# PROG328P.net
KiCad netlist of a schematic drawn in EAGLE
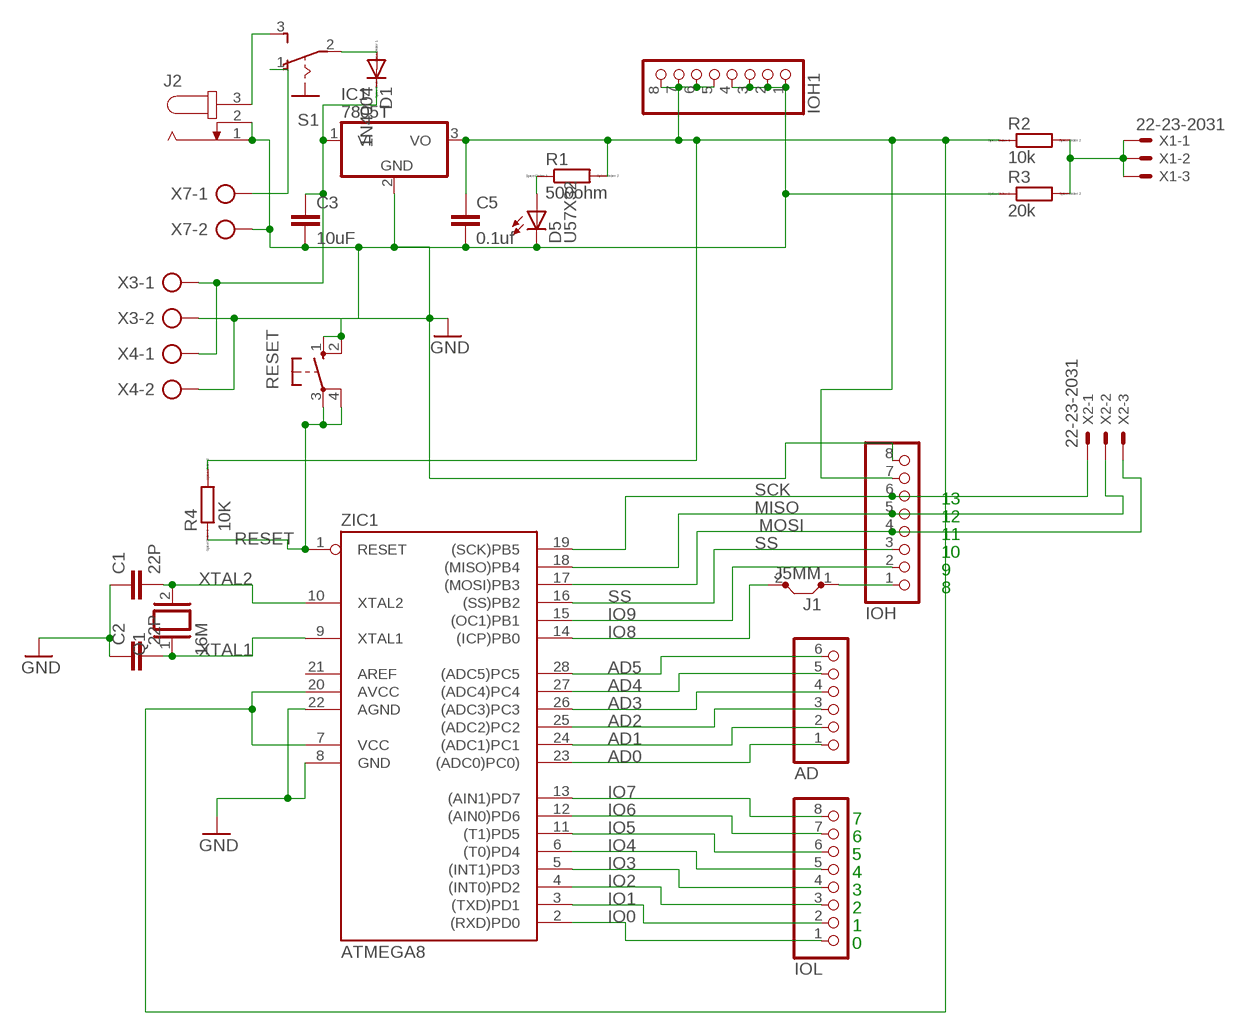
[diagram p0: schematic, sheet 1]

(export (version "E")
  (design (tool "Eeschema 10.0.6"))
  (components
    (comp (ref "AD")
      (value "PINHD-1X6")
      (footprint "eagle-import:1X06")
      (libsource (lib "eagle-import") (part "PINHD-1X6"))
    )
    (comp (ref "C1")
      (value "22P")
      (footprint "eagle-import:C2.5-6")
      (libsource (lib "eagle-import") (part "C2.5/6"))
    )
    (comp (ref "C2")
      (value "22P")
      (footprint "eagle-import:C2.5-6")
      (libsource (lib "eagle-import") (part "C2.5/6"))
    )
    (comp (ref "C3")
      (value "10uF")
      (footprint "eagle-import:C2.5-4")
      (libsource (lib "eagle-import") (part "C2.5/4"))
    )
    (comp (ref "C5")
      (value "0.1uf")
      (footprint "eagle-import:C2.5-4")
      (libsource (lib "eagle-import") (part "C2.5/4"))
    )
    (comp (ref "D1")
      (value "1N4004")
      (footprint "eagle-import:DO41-10")
      (libsource (lib "eagle-import") (part "1N4004"))
    )
    (comp (ref "D5")
      (value "U57X32")
      (footprint "eagle-import:U57X32")
      (libsource (lib "eagle-import") (part "U57X32"))
    )
    (comp (ref "IC1")
      (value "7805T")
      (footprint "eagle-import:TO220H")
      (libsource (lib "eagle-import") (part "78T05"))
    )
    (comp (ref "IOH")
      (value "PINHD-1X8")
      (footprint "eagle-import:1X08")
      (libsource (lib "eagle-import") (part "PINHD-1X8"))
    )
    (comp (ref "IOH1")
      (value "PINHD-1X8")
      (footprint "eagle-import:1X08")
      (libsource (lib "eagle-import") (part "PINHD-1X8"))
    )
    (comp (ref "IOL")
      (value "PINHD-1X8")
      (footprint "eagle-import:1X08")
      (libsource (lib "eagle-import") (part "PINHD-1X8"))
    )
    (comp (ref "J1")
      (value "J5MM")
      (footprint "eagle-import:05")
      (libsource (lib "eagle-import") (part "J5MM"))
    )
    (comp (ref "J2")
      (value "JACK-PLUG0")
      (footprint "eagle-import:SPC4077")
      (libsource (lib "eagle-import") (part "JACK-PLUG0"))
    )
    (comp (ref "Q1")
      (value "16M")
      (footprint "eagle-import:QS")
      (libsource (lib "eagle-import") (part "XTAL/S"))
    )
    (comp (ref "R1")
      (value "500ohm")
      (footprint "eagle-import:0207_10")
      (libsource (lib "eagle-import") (part "R0207/10"))
    )
    (comp (ref "R2")
      (value "10k")
      (footprint "eagle-import:0207_10")
      (libsource (lib "eagle-import") (part "R0207/10"))
    )
    (comp (ref "R3")
      (value "20k")
      (footprint "eagle-import:0207_10")
      (libsource (lib "eagle-import") (part "R0207/10"))
    )
    (comp (ref "R4")
      (value "10K")
      (footprint "eagle-import:0207_10")
      (libsource (lib "eagle-import") (part "R0207/10"))
    )
    (comp (ref "RESET")
      (value "10-XX")
      (footprint "eagle-import:B3F-10XX")
      (fields (field (name "MPN") "B3F-1000"))
      (libsource (lib "eagle-import") (part "10-XX"))
    )
    (comp (ref "S1")
      (value "255SB")
      (footprint "eagle-import:255SB")
      (libsource (lib "eagle-import") (part "255SB"))
    )
    (comp (ref "X1")
      (value "22-23-2031")
      (footprint "eagle-import:22-23-2031")
      (fields (field (name "MF") "MOLEX"))
      (libsource (lib "eagle-import") (part "22-23-2031"))
    )
    (comp (ref "X2")
      (value "22-23-2031")
      (footprint "eagle-import:22-23-2031")
      (fields (field (name "MF") "MOLEX"))
      (libsource (lib "eagle-import") (part "22-23-2031"))
    )
    (comp (ref "X3")
      (value "AK500/2-H")
      (footprint "eagle-import:AK500_2-H")
      (libsource (lib "eagle-import") (part "AK500/2-H"))
    )
    (comp (ref "X4")
      (value "AK500/2-H")
      (footprint "eagle-import:AK500_2-H")
      (libsource (lib "eagle-import") (part "AK500/2-H"))
    )
    (comp (ref "X7")
      (value "AK500/2-H")
      (footprint "eagle-import:AK500_2-H")
      (libsource (lib "eagle-import") (part "AK500/2-H"))
    )
    (comp (ref "ZIC1")
      (value "ATMEGA8")
      (footprint "eagle-import:DIL28-3")
      (libsource (lib "eagle-import") (part "AT90S4433P"))
    )
  )
  (nets
    (net (code "1") (name "/AD0") (class "Default")
      (node (ref "AD") (pin "1") (pinfunction "1_1") (pintype "passive"))
      (node (ref "ZIC1") (pin "23") (pinfunction "(ADC0)PC0)_23") (pintype "bidirectional"))
    )
    (net (code "2") (name "/AD1") (class "Default")
      (node (ref "AD") (pin "2") (pinfunction "2_2") (pintype "passive"))
      (node (ref "ZIC1") (pin "24") (pinfunction "(ADC1)PC1_24") (pintype "bidirectional"))
    )
    (net (code "3") (name "/AD2") (class "Default")
      (node (ref "AD") (pin "3") (pinfunction "3_3") (pintype "passive"))
      (node (ref "ZIC1") (pin "25") (pinfunction "(ADC2)PC2_25") (pintype "bidirectional"))
    )
    (net (code "4") (name "/AD3") (class "Default")
      (node (ref "AD") (pin "4") (pinfunction "4_4") (pintype "passive"))
      (node (ref "ZIC1") (pin "26") (pinfunction "(ADC3)PC3_26") (pintype "bidirectional"))
    )
    (net (code "5") (name "/AD4") (class "Default")
      (node (ref "AD") (pin "5") (pinfunction "5_5") (pintype "passive"))
      (node (ref "ZIC1") (pin "27") (pinfunction "(ADC4)PC4_27") (pintype "bidirectional"))
    )
    (net (code "6") (name "/AD5") (class "Default")
      (node (ref "AD") (pin "6") (pinfunction "6_6") (pintype "passive"))
      (node (ref "ZIC1") (pin "28") (pinfunction "(ADC5)PC5_28") (pintype "bidirectional"))
    )
    (net (code "7") (name "/IO0") (class "Default")
      (node (ref "IOL") (pin "1") (pinfunction "1_1") (pintype "passive"))
      (node (ref "ZIC1") (pin "2") (pinfunction "(RXD)PD0_2") (pintype "bidirectional"))
    )
    (net (code "8") (name "/IO1") (class "Default")
      (node (ref "IOL") (pin "2") (pinfunction "2_2") (pintype "passive"))
      (node (ref "ZIC1") (pin "3") (pinfunction "(TXD)PD1_3") (pintype "bidirectional"))
    )
    (net (code "9") (name "/IO2") (class "Default")
      (node (ref "IOL") (pin "3") (pinfunction "3_3") (pintype "passive"))
      (node (ref "ZIC1") (pin "4") (pinfunction "(INT0)PD2_4") (pintype "bidirectional"))
    )
    (net (code "10") (name "/IO3") (class "Default")
      (node (ref "IOL") (pin "4") (pinfunction "4_4") (pintype "passive"))
      (node (ref "ZIC1") (pin "5") (pinfunction "(INT1)PD3_5") (pintype "bidirectional"))
    )
    (net (code "11") (name "/IO4") (class "Default")
      (node (ref "IOL") (pin "5") (pinfunction "5_5") (pintype "passive"))
      (node (ref "ZIC1") (pin "6") (pinfunction "(T0)PD4_6") (pintype "bidirectional"))
    )
    (net (code "12") (name "/IO5") (class "Default")
      (node (ref "IOL") (pin "6") (pinfunction "6_6") (pintype "passive"))
      (node (ref "ZIC1") (pin "11") (pinfunction "(T1)PD5_11") (pintype "bidirectional"))
    )
    (net (code "13") (name "/IO6") (class "Default")
      (node (ref "IOL") (pin "7") (pinfunction "7_7") (pintype "passive"))
      (node (ref "ZIC1") (pin "12") (pinfunction "(AIN0)PD6_12") (pintype "bidirectional"))
    )
    (net (code "14") (name "/IO7") (class "Default")
      (node (ref "IOL") (pin "8") (pinfunction "8_8") (pintype "passive"))
      (node (ref "ZIC1") (pin "13") (pinfunction "(AIN1)PD7_13") (pintype "bidirectional"))
    )
    (net (code "15") (name "/IO8") (class "Default")
      (node (ref "J1") (pin "2") (pinfunction "2_2") (pintype "passive"))
      (node (ref "ZIC1") (pin "14") (pinfunction "(ICP)PB0_14") (pintype "bidirectional"))
    )
    (net (code "16") (name "/IO9") (class "Default")
      (node (ref "IOH") (pin "2") (pinfunction "2_2") (pintype "passive"))
      (node (ref "ZIC1") (pin "15") (pinfunction "(OC1)PB1_15") (pintype "bidirectional"))
    )
    (net (code "17") (name "/MISO") (class "Default")
      (node (ref "IOH") (pin "5") (pinfunction "5_5") (pintype "passive"))
      (node (ref "X2") (pin "2") (pinfunction "S_2") (pintype "passive"))
      (node (ref "ZIC1") (pin "18") (pinfunction "(MISO)PB4_18") (pintype "bidirectional"))
    )
    (net (code "18") (name "/MOSI") (class "Default")
      (node (ref "IOH") (pin "4") (pinfunction "4_4") (pintype "passive"))
      (node (ref "X2") (pin "3") (pinfunction "S_3") (pintype "passive"))
      (node (ref "ZIC1") (pin "17") (pinfunction "(MOSI)PB3_17") (pintype "bidirectional"))
    )
    (net (code "19") (name "/RESET") (class "Default")
      (node (ref "R4") (pin "1") (pinfunction "1_1") (pintype "passive"))
      (node (ref "RESET") (pin "3") (pinfunction "P_3") (pintype "passive"))
      (node (ref "RESET") (pin "4") (pinfunction "P1_4") (pintype "passive"))
      (node (ref "ZIC1") (pin "1") (pinfunction "RESET_1") (pintype "input"))
    )
    (net (code "20") (name "/SCK") (class "Default")
      (node (ref "IOH") (pin "6") (pinfunction "6_6") (pintype "passive"))
      (node (ref "X2") (pin "1") (pinfunction "S_1") (pintype "passive"))
      (node (ref "ZIC1") (pin "19") (pinfunction "(SCK)PB5_19") (pintype "bidirectional"))
    )
    (net (code "21") (name "/SS") (class "Default")
      (node (ref "IOH") (pin "3") (pinfunction "3_3") (pintype "passive"))
      (node (ref "ZIC1") (pin "16") (pinfunction "(SS)PB2_16") (pintype "bidirectional"))
    )
    (net (code "22") (name "/XTAL1") (class "Default")
      (node (ref "C2") (pin "2") (pinfunction "2_2") (pintype "passive"))
      (node (ref "Q1") (pin "1") (pinfunction "1_1") (pintype "passive"))
      (node (ref "ZIC1") (pin "9") (pinfunction "XTAL1_9") (pintype "bidirectional"))
    )
    (net (code "23") (name "/XTAL2") (class "Default")
      (node (ref "C1") (pin "2") (pinfunction "2_2") (pintype "passive"))
      (node (ref "Q1") (pin "2") (pinfunction "2_2") (pintype "passive"))
      (node (ref "ZIC1") (pin "10") (pinfunction "XTAL2_10") (pintype "bidirectional"))
    )
    (net (code "24") (name "GND") (class "Default")
      (node (ref "C1") (pin "1") (pinfunction "1_1") (pintype "passive"))
      (node (ref "C2") (pin "1") (pinfunction "1_1") (pintype "passive"))
      (node (ref "C3") (pin "2") (pinfunction "2_2") (pintype "passive"))
      (node (ref "C5") (pin "2") (pinfunction "2_2") (pintype "passive"))
      (node (ref "D5") (pin "K") (pinfunction "C_K") (pintype "passive"))
      (node (ref "IC1") (pin "2") (pinfunction "GND_2") (pintype "passive"))
      (node (ref "IOH") (pin "8") (pinfunction "8_8") (pintype "passive"))
      (node (ref "IOH1") (pin "1") (pinfunction "1_1") (pintype "passive"))
      (node (ref "IOH1") (pin "2") (pinfunction "2_2") (pintype "passive"))
      (node (ref "IOH1") (pin "3") (pinfunction "3_3") (pintype "passive"))
      (node (ref "IOH1") (pin "4") (pinfunction "4_4") (pintype "passive"))
      (node (ref "J2") (pin "1") (pinfunction "1_1") (pintype "passive"))
      (node (ref "J2") (pin "2") (pinfunction "2_2") (pintype "passive"))
      (node (ref "R3") (pin "1") (pinfunction "1_1") (pintype "passive"))
      (node (ref "RESET") (pin "1") (pinfunction "S_1") (pintype "passive"))
      (node (ref "RESET") (pin "2") (pinfunction "S1_2") (pintype "passive"))
      (node (ref "X3") (pin "2") (pinfunction "KL_2") (pintype "passive"))
      (node (ref "X4") (pin "2") (pinfunction "KL_2") (pintype "passive"))
      (node (ref "X7") (pin "2") (pinfunction "KL_2") (pintype "passive"))
      (node (ref "ZIC1") (pin "22") (pinfunction "AGND_22") (pintype "power_in"))
      (node (ref "ZIC1") (pin "8") (pinfunction "GND_8") (pintype "power_in"))
    )
    (net (code "25") (name "Net-(D5-PadA)") (class "Default")
      (node (ref "D5") (pin "A") (pinfunction "A_A") (pintype "passive"))
      (node (ref "R1") (pin "1") (pinfunction "1_1") (pintype "passive"))
    )
    (net (code "26") (name "Net-(IC1-VI)") (class "Default")
      (node (ref "C3") (pin "1") (pinfunction "1_1") (pintype "passive"))
      (node (ref "D1") (pin "C") (pinfunction "C_C") (pintype "passive"))
      (node (ref "IC1") (pin "1") (pinfunction "VI_1") (pintype "input"))
      (node (ref "X3") (pin "1") (pinfunction "KL_1") (pintype "passive"))
      (node (ref "X4") (pin "1") (pinfunction "KL_1") (pintype "passive"))
    )
    (net (code "27") (name "Net-(IC1-VO)") (class "Default")
      (node (ref "C5") (pin "1") (pinfunction "1_1") (pintype "passive"))
      (node (ref "IC1") (pin "3") (pinfunction "VO_3") (pintype "passive"))
      (node (ref "IOH") (pin "7") (pinfunction "7_7") (pintype "passive"))
      (node (ref "IOH1") (pin "5") (pinfunction "5_5") (pintype "passive"))
      (node (ref "IOH1") (pin "6") (pinfunction "6_6") (pintype "passive"))
      (node (ref "IOH1") (pin "7") (pinfunction "7_7") (pintype "passive"))
      (node (ref "IOH1") (pin "8") (pinfunction "8_8") (pintype "passive"))
      (node (ref "R1") (pin "2") (pinfunction "2_2") (pintype "passive"))
      (node (ref "R2") (pin "1") (pinfunction "1_1") (pintype "passive"))
      (node (ref "R4") (pin "2") (pinfunction "2_2") (pintype "passive"))
      (node (ref "ZIC1") (pin "20") (pinfunction "AVCC_20") (pintype "power_in"))
      (node (ref "ZIC1") (pin "7") (pinfunction "VCC_7") (pintype "power_in"))
    )
    (net (code "28") (name "Net-(IOH-Pad1)") (class "Default")
      (node (ref "IOH") (pin "1") (pinfunction "1_1") (pintype "passive"))
      (node (ref "J1") (pin "1") (pinfunction "1_1") (pintype "passive"))
    )
    (net (code "29") (name "Net-(S1-O)") (class "Default")
      (node (ref "S1") (pin "1") (pinfunction "O_1") (pintype "passive"))
      (node (ref "X7") (pin "1") (pinfunction "KL_1") (pintype "passive"))
    )
    (net (code "30") (name "Net-(S1-P)") (class "Default")
      (node (ref "D1") (pin "A") (pinfunction "A_A") (pintype "passive"))
      (node (ref "S1") (pin "2") (pinfunction "P_2") (pintype "passive"))
    )
    (net (code "31") (name "Net-(S1-S)") (class "Default")
      (node (ref "J2") (pin "3") (pinfunction "3_3") (pintype "passive"))
      (node (ref "S1") (pin "3") (pinfunction "S_3") (pintype "passive"))
    )
    (net (code "32") (name "Net-(X1A-S)") (class "Default")
      (node (ref "R2") (pin "2") (pinfunction "2_2") (pintype "passive"))
      (node (ref "R3") (pin "2") (pinfunction "2_2") (pintype "passive"))
      (node (ref "X1") (pin "1") (pinfunction "S_1") (pintype "passive"))
      (node (ref "X1") (pin "2") (pinfunction "S_2") (pintype "passive"))
      (node (ref "X1") (pin "3") (pinfunction "S_3") (pintype "passive"))
    )
    (net (code "33") (name "unconnected-(ZIC1-AREF-Pad21)") (class "Default")
      (node (ref "ZIC1") (pin "21") (pinfunction "AREF_21") (pintype "passive"))
    )
  )
)
